# Skematik_Project_Akhir.net
KiCad netlist of a schematic drawn in EAGLE
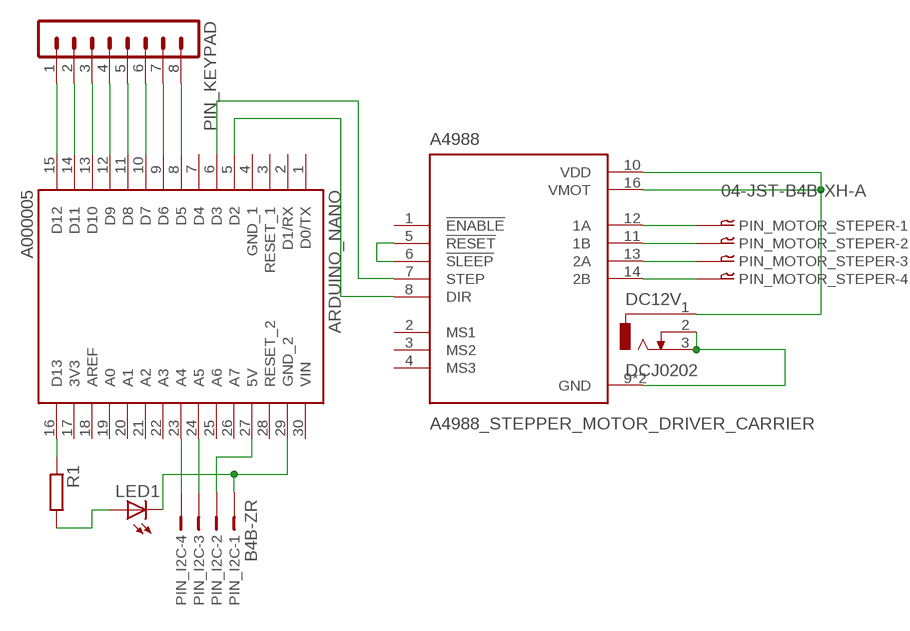
[diagram p0: schematic, sheet 1]

(export (version "E")
  (design (tool "Eeschema 10.0.6"))
  (components
    (comp (ref "A4988")
      (value "A4988_STEPPER_MOTOR_DRIVER_CARRIER")
      (footprint "eagle-import:MODULE_A4988_STEPPER_MOTOR_DRIVER_CARRIER")
      (fields (field (name "MF") "Pololu") (field (name "MP") "A4988 STEPPER MOTOR DRIVER CARRIER"))
      (libsource (lib "eagle-import") (part "A4988_STEPPER_MOTOR_DRIVER_CARRIER"))
    )
    (comp (ref "ARDUINO_NANO")
      (value "A000005")
      (footprint "eagle-import:MODULE_A000005")
      (fields (field (name "MF") "Arduino"))
      (libsource (lib "eagle-import") (part "A000005"))
    )
    (comp (ref "DC12V")
      (value "DCJ0202")
      (footprint "eagle-import:DCJ0202")
      (libsource (lib "eagle-import") (part "DCJ0202"))
    )
    (comp (ref "LED1")
      (value "LED3MM")
      (footprint "eagle-import:LED3MM")
      (libsource (lib "eagle-import") (part "LED3MM"))
    )
    (comp (ref "PIN_I2C")
      (value "B4B-ZR")
      (footprint "eagle-import:B4B-ZR")
      (fields (field (name "MF") "FARNELL") (field (name "MPN") "B4B-ZR(LF)(SN)"))
      (libsource (lib "eagle-import") (part "?4B-ZRB"))
    )
    (comp (ref "PIN_KEYPAD")
      (value "MA08-1")
      (footprint "eagle-import:MA08-1")
      (libsource (lib "eagle-import") (part "MA08-1"))
    )
    (comp (ref "PIN_MOTOR_STEPER")
      (value "04-JST-B4B-XH-A")
      (footprint "eagle-import:B4B-XH")
      (libsource (lib "eagle-import") (part "04-JST-B4B-XH-A"))
    )
    (comp (ref "R1")
      (value "R-EU_0207/10")
      (footprint "eagle-import:0207_10")
      (libsource (lib "eagle-import") (part "R-EU_0207/10"))
    )
  )
  (nets
    (net (code "1") (name "/3V3") (class "Default")
      (node (ref "ARDUINO_NANO") (pin "17") (pinfunction "3V3_17") (pintype "power_in"))
    )
    (net (code "2") (name "/GND_1") (class "Default")
      (node (ref "ARDUINO_NANO") (pin "4") (pinfunction "GND_1_4") (pintype "power_in"))
    )
    (net (code "3") (name "/VIN") (class "Default")
      (node (ref "ARDUINO_NANO") (pin "30") (pinfunction "VIN_30") (pintype "power_in"))
    )
    (net (code "4") (name "Net-(A4988-1A)") (class "Default")
      (node (ref "A4988") (pin "12") (pinfunction "1A_12") (pintype "output"))
      (node (ref "PIN_MOTOR_STEPER") (pin "P$1") (pinfunction "1_P$1") (pintype "passive"))
    )
    (net (code "5") (name "Net-(A4988-1B)") (class "Default")
      (node (ref "A4988") (pin "11") (pinfunction "1B_11") (pintype "output"))
      (node (ref "PIN_MOTOR_STEPER") (pin "P$2") (pinfunction "1_P$2") (pintype "passive"))
    )
    (net (code "6") (name "Net-(A4988-2A)") (class "Default")
      (node (ref "A4988") (pin "13") (pinfunction "2A_13") (pintype "output"))
      (node (ref "PIN_MOTOR_STEPER") (pin "P$3") (pinfunction "1_P$3") (pintype "passive"))
    )
    (net (code "7") (name "Net-(A4988-2B)") (class "Default")
      (node (ref "A4988") (pin "14") (pinfunction "2B_14") (pintype "output"))
      (node (ref "PIN_MOTOR_STEPER") (pin "P$4") (pinfunction "1_P$4") (pintype "passive"))
    )
    (net (code "8") (name "Net-(A4988-DIR)") (class "Default")
      (node (ref "A4988") (pin "8") (pinfunction "DIR_8") (pintype "input"))
      (node (ref "ARDUINO_NANO") (pin "5") (pinfunction "D2_5") (pintype "bidirectional"))
    )
    (net (code "9") (name "Net-(A4988-GND-Pad15)") (class "Default")
      (node (ref "A4988") (pin "15") (pinfunction "GND_15") (pintype "power_in"))
      (node (ref "A4988") (pin "9") (pinfunction "GND_9") (pintype "power_in"))
      (node (ref "DC12V") (pin "2") (pinfunction "2_2") (pintype "passive"))
      (node (ref "DC12V") (pin "3") (pinfunction "3_3") (pintype "passive"))
    )
    (net (code "10") (name "Net-(A4988-STEP)") (class "Default")
      (node (ref "A4988") (pin "7") (pinfunction "STEP_7") (pintype "input"))
      (node (ref "ARDUINO_NANO") (pin "6") (pinfunction "D3_6") (pintype "bidirectional"))
    )
    (net (code "11") (name "Net-(A4988-VDD)") (class "Default")
      (node (ref "A4988") (pin "10") (pinfunction "VDD_10") (pintype "power_in"))
      (node (ref "A4988") (pin "16") (pinfunction "VMOT_16") (pintype "power_in"))
      (node (ref "DC12V") (pin "1") (pinfunction "1_1") (pintype "passive"))
    )
    (net (code "12") (name "Net-(A4988-~{RESET})") (class "Default")
      (node (ref "A4988") (pin "5") (pinfunction "~{RESET}_5") (pintype "input"))
      (node (ref "A4988") (pin "6") (pinfunction "~{SLEEP}_6") (pintype "input"))
    )
    (net (code "13") (name "Net-(ARDUINO_NANO-5V)") (class "Default")
      (node (ref "ARDUINO_NANO") (pin "27") (pinfunction "5V_27") (pintype "power_in"))
      (node (ref "PIN_I2C") (pin "2") (pinfunction "1_2") (pintype "passive"))
    )
    (net (code "14") (name "Net-(ARDUINO_NANO-A4)") (class "Default")
      (node (ref "ARDUINO_NANO") (pin "23") (pinfunction "A4_23") (pintype "input"))
      (node (ref "PIN_I2C") (pin "4") (pinfunction "1_4") (pintype "passive"))
    )
    (net (code "15") (name "Net-(ARDUINO_NANO-A5)") (class "Default")
      (node (ref "ARDUINO_NANO") (pin "24") (pinfunction "A5_24") (pintype "input"))
      (node (ref "PIN_I2C") (pin "3") (pinfunction "1_3") (pintype "passive"))
    )
    (net (code "16") (name "Net-(ARDUINO_NANO-D5)") (class "Default")
      (node (ref "ARDUINO_NANO") (pin "8") (pinfunction "D5_8") (pintype "bidirectional"))
      (node (ref "PIN_KEYPAD") (pin "8") (pinfunction "8_8") (pintype "passive"))
    )
    (net (code "17") (name "Net-(ARDUINO_NANO-D6)") (class "Default")
      (node (ref "ARDUINO_NANO") (pin "9") (pinfunction "D6_9") (pintype "bidirectional"))
      (node (ref "PIN_KEYPAD") (pin "7") (pinfunction "7_7") (pintype "passive"))
    )
    (net (code "18") (name "Net-(ARDUINO_NANO-D7)") (class "Default")
      (node (ref "ARDUINO_NANO") (pin "10") (pinfunction "D7_10") (pintype "bidirectional"))
      (node (ref "PIN_KEYPAD") (pin "6") (pinfunction "6_6") (pintype "passive"))
    )
    (net (code "19") (name "Net-(ARDUINO_NANO-D8)") (class "Default")
      (node (ref "ARDUINO_NANO") (pin "11") (pinfunction "D8_11") (pintype "bidirectional"))
      (node (ref "PIN_KEYPAD") (pin "5") (pinfunction "5_5") (pintype "passive"))
    )
    (net (code "20") (name "Net-(ARDUINO_NANO-D9)") (class "Default")
      (node (ref "ARDUINO_NANO") (pin "12") (pinfunction "D9_12") (pintype "bidirectional"))
      (node (ref "PIN_KEYPAD") (pin "4") (pinfunction "4_4") (pintype "passive"))
    )
    (net (code "21") (name "Net-(ARDUINO_NANO-D10)") (class "Default")
      (node (ref "ARDUINO_NANO") (pin "13") (pinfunction "D10_13") (pintype "bidirectional"))
      (node (ref "PIN_KEYPAD") (pin "3") (pinfunction "3_3") (pintype "passive"))
    )
    (net (code "22") (name "Net-(ARDUINO_NANO-D11)") (class "Default")
      (node (ref "ARDUINO_NANO") (pin "14") (pinfunction "D11_14") (pintype "bidirectional"))
      (node (ref "PIN_KEYPAD") (pin "2") (pinfunction "2_2") (pintype "passive"))
    )
    (net (code "23") (name "Net-(ARDUINO_NANO-D12)") (class "Default")
      (node (ref "ARDUINO_NANO") (pin "15") (pinfunction "D12_15") (pintype "bidirectional"))
      (node (ref "PIN_KEYPAD") (pin "1") (pinfunction "1_1") (pintype "passive"))
    )
    (net (code "24") (name "Net-(ARDUINO_NANO-D13)") (class "Default")
      (node (ref "ARDUINO_NANO") (pin "16") (pinfunction "D13_16") (pintype "bidirectional"))
      (node (ref "R1") (pin "1") (pinfunction "1_1") (pintype "passive"))
    )
    (net (code "25") (name "Net-(ARDUINO_NANO-GND_2)") (class "Default")
      (node (ref "ARDUINO_NANO") (pin "29") (pinfunction "GND_2_29") (pintype "power_in"))
      (node (ref "LED1") (pin "K") (pinfunction "C_K") (pintype "passive"))
      (node (ref "PIN_I2C") (pin "1") (pinfunction "1_1") (pintype "passive"))
    )
    (net (code "26") (name "Net-(LED1-PadA)") (class "Default")
      (node (ref "LED1") (pin "A") (pinfunction "A_A") (pintype "passive"))
      (node (ref "R1") (pin "2") (pinfunction "2_2") (pintype "passive"))
    )
    (net (code "27") (name "unconnected-(A4988-MS1-Pad2)") (class "Default")
      (node (ref "A4988") (pin "2") (pinfunction "MS1_2") (pintype "input"))
    )
    (net (code "28") (name "unconnected-(A4988-MS2-Pad3)") (class "Default")
      (node (ref "A4988") (pin "3") (pinfunction "MS2_3") (pintype "input"))
    )
    (net (code "29") (name "unconnected-(A4988-MS3-Pad4)") (class "Default")
      (node (ref "A4988") (pin "4") (pinfunction "MS3_4") (pintype "input"))
    )
    (net (code "30") (name "unconnected-(A4988-~{ENABLE}-Pad1)") (class "Default")
      (node (ref "A4988") (pin "1") (pinfunction "~{ENABLE}_1") (pintype "input"))
    )
    (net (code "31") (name "unconnected-(ARDUINO_NANO-A0-Pad19)") (class "Default")
      (node (ref "ARDUINO_NANO") (pin "19") (pinfunction "A0_19") (pintype "input"))
    )
    (net (code "32") (name "unconnected-(ARDUINO_NANO-A1-Pad20)") (class "Default")
      (node (ref "ARDUINO_NANO") (pin "20") (pinfunction "A1_20") (pintype "input"))
    )
    (net (code "33") (name "unconnected-(ARDUINO_NANO-A2-Pad21)") (class "Default")
      (node (ref "ARDUINO_NANO") (pin "21") (pinfunction "A2_21") (pintype "input"))
    )
    (net (code "34") (name "unconnected-(ARDUINO_NANO-A3-Pad22)") (class "Default")
      (node (ref "ARDUINO_NANO") (pin "22") (pinfunction "A3_22") (pintype "input"))
    )
    (net (code "35") (name "unconnected-(ARDUINO_NANO-A6-Pad25)") (class "Default")
      (node (ref "ARDUINO_NANO") (pin "25") (pinfunction "A6_25") (pintype "input"))
    )
    (net (code "36") (name "unconnected-(ARDUINO_NANO-A7-Pad26)") (class "Default")
      (node (ref "ARDUINO_NANO") (pin "26") (pinfunction "A7_26") (pintype "input"))
    )
    (net (code "37") (name "unconnected-(ARDUINO_NANO-AREF-Pad18)") (class "Default")
      (node (ref "ARDUINO_NANO") (pin "18") (pinfunction "AREF_18") (pintype "input"))
    )
    (net (code "38") (name "unconnected-(ARDUINO_NANO-D0{slash}TX-Pad1)") (class "Default")
      (node (ref "ARDUINO_NANO") (pin "1") (pinfunction "D0/TX_1") (pintype "bidirectional"))
    )
    (net (code "39") (name "unconnected-(ARDUINO_NANO-D1{slash}RX-Pad2)") (class "Default")
      (node (ref "ARDUINO_NANO") (pin "2") (pinfunction "D1/RX_2") (pintype "bidirectional"))
    )
    (net (code "40") (name "unconnected-(ARDUINO_NANO-D4-Pad7)") (class "Default")
      (node (ref "ARDUINO_NANO") (pin "7") (pinfunction "D4_7") (pintype "bidirectional"))
    )
    (net (code "41") (name "unconnected-(ARDUINO_NANO-RESET_1-Pad3)") (class "Default")
      (node (ref "ARDUINO_NANO") (pin "3") (pinfunction "RESET_1_3") (pintype "input"))
    )
    (net (code "42") (name "unconnected-(ARDUINO_NANO-RESET_2-Pad28)") (class "Default")
      (node (ref "ARDUINO_NANO") (pin "28") (pinfunction "RESET_2_28") (pintype "input"))
    )
  )
)
